# power.net
KiCad netlist of a schematic drawn in Altium Designer
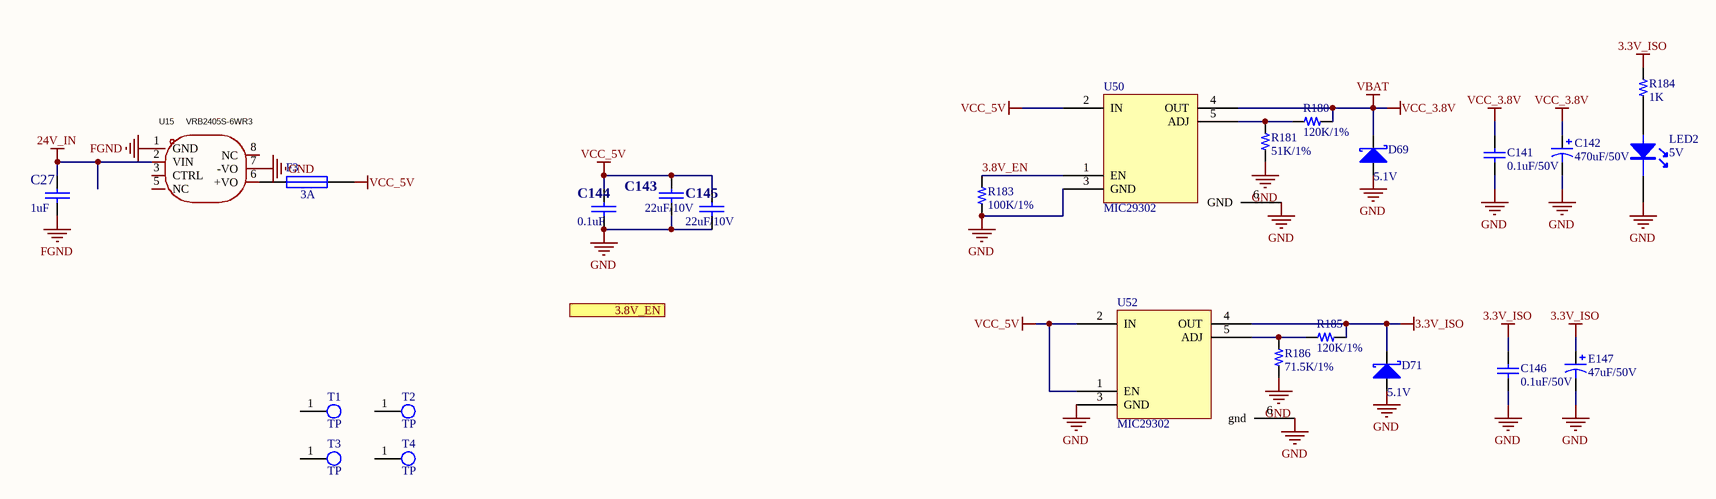
[diagram p0: power.SchDoc]

(export (version "E")
  (design (tool "Eeschema 10.0.6"))
  (components
    (comp (ref "C27")
      (value "1uF")
      (footprint "0603C")
      (description "Capacitor")
      (libsource (lib "*") (part "CAP"))
    )
    (comp (ref "C141")
      (value "0.1uF/50V")
      (footprint "0603C")
      (description "Capacitor")
      (fields (field (name "PUBLISHER") "Altium Limited"))
      (libsource (lib "Miscellaneous Devices") (part "Cap"))
    )
    (comp (ref "C142")
      (value "470uF/50V")
      (footprint "Φ10×10")
      (description "Polarized Capacitor (Radial)")
      (fields (field (name "PUBLISHER") "Altium Limited"))
      (libsource (lib "Miscellaneous Devices") (part "Cap Pol1"))
    )
    (comp (ref "C143")
      (value "22uF/10V")
      (footprint "1210C")
      (description "Capacitor")
      (libsource (lib "*") (part "CAP"))
    )
    (comp (ref "C144")
      (value "0.1uF")
      (footprint "0603C")
      (description "Capacitor")
      (libsource (lib "*") (part "CAP"))
    )
    (comp (ref "C145")
      (value "22uF/10V")
      (footprint "1210C")
      (description "Capacitor")
      (libsource (lib "*") (part "CAP"))
    )
    (comp (ref "C146")
      (value "0.1uF/50V")
      (footprint "0603C")
      (description "Capacitor")
      (fields (field (name "PUBLISHER") "Altium Limited"))
      (libsource (lib "Miscellaneous Devices") (part "Cap"))
    )
    (comp (ref "D69")
      (value "5.1V")
      (footprint "SMA")
      (description "Schottky Diode")
      (libsource (lib "*") (part "DIODE S"))
    )
    (comp (ref "D71")
      (value "5.1V")
      (footprint "SMA")
      (description "Schottky Diode")
      (libsource (lib "*") (part "DIODE S"))
    )
    (comp (ref "E147")
      (value "47uF/50V")
      (footprint "Φ10×10")
      (description "Polarized Capacitor (Radial)")
      (fields (field (name "PUBLISHER") "Altium Limited"))
      (libsource (lib "Miscellaneous Devices") (part "Cap Pol1"))
    )
    (comp (ref "F3")
      (value "3A")
      (footprint "1812-F")
      (description "Fuse")
      (fields (field (name "PUBLISHER") "Altium Limited"))
      (libsource (lib "Miscellaneous Devices") (part "Fuse 1"))
    )
    (comp (ref "LED2") (value "5V") (footprint "0603LED") (libsource (lib "*") (part "LED")))
    (comp (ref "R180")
      (value "120K/1%")
      (footprint "0603R")
      (description "R")
      (libsource (lib "JRJ_1") (part "R"))
    )
    (comp (ref "R181")
      (value "51K/1%")
      (footprint "0603R")
      (description "R")
      (libsource (lib "JRJ_1") (part "R"))
    )
    (comp (ref "R183")
      (value "100K/1%")
      (footprint "0603R")
      (description "R")
      (libsource (lib "JRJ_1") (part "R"))
    )
    (comp (ref "R184")
      (value "1K")
      (footprint "0603R")
      (description "R")
      (libsource (lib "JRJ_1") (part "R"))
    )
    (comp (ref "R185")
      (value "120K/1%")
      (footprint "0603R")
      (description "R")
      (libsource (lib "JRJ_1") (part "R"))
    )
    (comp (ref "R186")
      (value "71.5K/1%")
      (footprint "0603R")
      (description "R")
      (libsource (lib "JRJ_1") (part "R"))
    )
    (comp (ref "T1") (value "TP") (footprint "M3") (libsource (lib "Schlib_20110825") (part "TP")))
    (comp (ref "T2") (value "TP") (footprint "M3") (libsource (lib "Schlib_20110825") (part "TP")))
    (comp (ref "T3") (value "TP") (footprint "M3") (libsource (lib "Schlib_20110825") (part "TP")))
    (comp (ref "T4") (value "TP") (footprint "M3") (libsource (lib "Schlib_20110825") (part "TP")))
    (comp (ref "U15")
      (value "VRB2405S-6WR3")
      (footprint "PWRM-TH_VRB2405S-6WR3")
      (fields (field (name "MANUFACTURER") "YLPTEC(易川)") (field (name "POWER") "6W"))
      (libsource (lib "altium-import") (part "root_0_VRB2405S-6WR3_1_"))
    )
    (comp (ref "U50")
      (value "MIC29302")
      (footprint "TO228P1435X457-6N")
      (libsource (lib "power") (part "MIC29302"))
    )
    (comp (ref "U52")
      (value "MIC29302")
      (footprint "TO228P1435X457-6N")
      (libsource (lib "power") (part "MIC29302"))
    )
  )
  (nets
    (net (code "1") (name "/3.8V_EN") (class "Default")
      (node (ref "R183") (pin "2") (pintype "passive"))
      (node (ref "U50") (pin "1") (pinfunction "EN_1") (pintype "passive"))
    )
    (net (code "2") (name "3.3V_ISO") (class "Default")
      (node (ref "C146") (pin "2") (pinfunction "2_2") (pintype "passive"))
      (node (ref "D71") (pin "2") (pinfunction "K_2") (pintype "passive"))
      (node (ref "E147") (pin "1") (pinfunction "1_1") (pintype "passive"))
      (node (ref "R184") (pin "2") (pintype "passive"))
      (node (ref "R185") (pin "1") (pintype "passive"))
      (node (ref "U52") (pin "4") (pinfunction "OUT_4") (pintype "passive"))
    )
    (net (code "3") (name "24V_IN") (class "Default")
      (node (ref "C27") (pin "2") (pinfunction "2_2") (pintype "passive"))
      (node (ref "U15") (pin "2") (pinfunction "VIN_2") (pintype "passive"))
    )
    (net (code "4") (name "FGND") (class "Default")
      (node (ref "C27") (pin "1") (pinfunction "1_1") (pintype "passive"))
      (node (ref "U15") (pin "1") (pinfunction "GND_1") (pintype "passive"))
    )
    (net (code "5") (name "GND") (class "Default")
      (node (ref "C141") (pin "1") (pinfunction "1_1") (pintype "passive"))
      (node (ref "C142") (pin "2") (pinfunction "2_2") (pintype "passive"))
      (node (ref "C143") (pin "2") (pinfunction "2_2") (pintype "passive"))
      (node (ref "C144") (pin "2") (pinfunction "2_2") (pintype "passive"))
      (node (ref "C145") (pin "2") (pinfunction "2_2") (pintype "passive"))
      (node (ref "C146") (pin "1") (pinfunction "1_1") (pintype "passive"))
      (node (ref "D69") (pin "1") (pinfunction "A_1") (pintype "passive"))
      (node (ref "D71") (pin "1") (pinfunction "A_1") (pintype "passive"))
      (node (ref "E147") (pin "2") (pinfunction "2_2") (pintype "passive"))
      (node (ref "LED2") (pin "2") (pinfunction "2_2") (pintype "passive"))
      (node (ref "R181") (pin "1") (pintype "passive"))
      (node (ref "R183") (pin "1") (pintype "passive"))
      (node (ref "R186") (pin "1") (pintype "passive"))
      (node (ref "U15") (pin "7") (pinfunction "-VO_7") (pintype "passive"))
      (node (ref "U50") (pin "3") (pinfunction "GND_3") (pintype "passive"))
      (node (ref "U50") (pin "6") (pinfunction "gnd_6") (pintype "passive"))
      (node (ref "U52") (pin "3") (pinfunction "GND_3") (pintype "passive"))
      (node (ref "U52") (pin "6") (pinfunction "gnd_6") (pintype "passive"))
    )
    (net (code "6") (name "Net-(LED2-Pad1)") (class "Default")
      (node (ref "LED2") (pin "1") (pinfunction "1_1") (pintype "passive"))
      (node (ref "R184") (pin "1") (pintype "passive"))
    )
    (net (code "7") (name "Net-(U15-+VO)") (class "Default")
      (node (ref "F3") (pin "1") (pinfunction "1_1") (pintype "passive"))
      (node (ref "U15") (pin "6") (pinfunction "+VO_6") (pintype "passive"))
    )
    (net (code "8") (name "Net-(U50-ADJ)") (class "Default")
      (node (ref "R180") (pin "2") (pintype "passive"))
      (node (ref "R181") (pin "2") (pintype "passive"))
      (node (ref "U50") (pin "5") (pinfunction "ADJ_5") (pintype "passive"))
    )
    (net (code "9") (name "Net-(U52-ADJ)") (class "Default")
      (node (ref "R185") (pin "2") (pintype "passive"))
      (node (ref "R186") (pin "2") (pintype "passive"))
      (node (ref "U52") (pin "5") (pinfunction "ADJ_5") (pintype "passive"))
    )
    (net (code "10") (name "VBAT") (class "Default")
      (node (ref "C141") (pin "2") (pinfunction "2_2") (pintype "passive"))
      (node (ref "C142") (pin "1") (pinfunction "1_1") (pintype "passive"))
      (node (ref "D69") (pin "2") (pinfunction "K_2") (pintype "passive"))
      (node (ref "R180") (pin "1") (pintype "passive"))
      (node (ref "U50") (pin "4") (pinfunction "OUT_4") (pintype "passive"))
    )
    (net (code "11") (name "VCC_5V") (class "Default")
      (node (ref "C143") (pin "1") (pinfunction "1_1") (pintype "passive"))
      (node (ref "C144") (pin "1") (pinfunction "1_1") (pintype "passive"))
      (node (ref "C145") (pin "1") (pinfunction "1_1") (pintype "passive"))
      (node (ref "F3") (pin "2") (pinfunction "2_2") (pintype "passive"))
      (node (ref "U50") (pin "2") (pinfunction "IN_2") (pintype "passive"))
      (node (ref "U52") (pin "1") (pinfunction "EN_1") (pintype "passive"))
      (node (ref "U52") (pin "2") (pinfunction "IN_2") (pintype "passive"))
    )
    (net (code "12") (name "unconnected-(T1-Pad1)") (class "Default")
      (node (ref "T1") (pin "1") (pintype "passive"))
    )
    (net (code "13") (name "unconnected-(T2-Pad1)") (class "Default")
      (node (ref "T2") (pin "1") (pintype "passive"))
    )
    (net (code "14") (name "unconnected-(T3-Pad1)") (class "Default")
      (node (ref "T3") (pin "1") (pintype "passive"))
    )
    (net (code "15") (name "unconnected-(T4-Pad1)") (class "Default")
      (node (ref "T4") (pin "1") (pintype "passive"))
    )
    (net (code "16") (name "unconnected-(U15-CTRL-Pad3)") (class "Default")
      (node (ref "U15") (pin "3") (pinfunction "CTRL_3") (pintype "passive"))
    )
    (net (code "17") (name "unconnected-(U15-NC-Pad5)") (class "Default")
      (node (ref "U15") (pin "5") (pinfunction "NC_5") (pintype "passive"))
    )
    (net (code "18") (name "unconnected-(U15-NC-Pad8)") (class "Default")
      (node (ref "U15") (pin "8") (pinfunction "NC_8") (pintype "passive"))
    )
  )
)
